# Fuente_Simetrica.net
KiCad netlist of a schematic drawn in Altium Designer
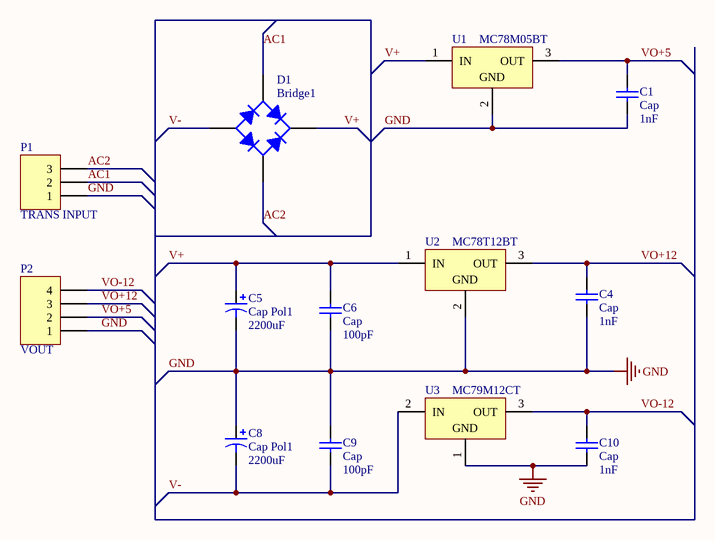
[diagram p0: Fuente Simetrica.SchDoc]

(export (version "E")
  (design (tool "Eeschema 10.0.6"))
  (components
    (comp (ref "C1")
      (value "Cap")
      (footprint "RAD-0.2")
      (description "Capacitor")
      (fields (field (name "ALTIUM_VALUE") "1nF") (field (name "PUBLISHER") "Altium Limited"))
      (libsource (lib "Miscellaneous Devices") (part "Cap"))
    )
    (comp (ref "C4")
      (value "Cap")
      (footprint "RAD-0.2")
      (description "Capacitor")
      (fields (field (name "ALTIUM_VALUE") "1nF") (field (name "PUBLISHER") "Altium Limited"))
      (libsource (lib "Miscellaneous Devices") (part "Cap"))
    )
    (comp (ref "C5")
      (value "Cap Pol1")
      (footprint "RB5-10.5")
      (description "Polarized Capacitor (Radial)")
      (fields (field (name "ALTIUM_VALUE") "2200uF") (field (name "PUBLISHER") "Altium Limited"))
      (libsource (lib "Miscellaneous Devices") (part "Cap Pol1"))
    )
    (comp (ref "C6")
      (value "Cap")
      (footprint "RAD-0.2")
      (description "Capacitor")
      (fields (field (name "ALTIUM_VALUE") "100pF") (field (name "PUBLISHER") "Altium Limited"))
      (libsource (lib "Miscellaneous Devices") (part "Cap"))
    )
    (comp (ref "C8")
      (value "Cap Pol1")
      (footprint "RB5-10.5")
      (description "Polarized Capacitor (Radial)")
      (fields (field (name "ALTIUM_VALUE") "2200uF") (field (name "PUBLISHER") "Altium Limited"))
      (libsource (lib "Miscellaneous Devices") (part "Cap Pol1"))
    )
    (comp (ref "C9")
      (value "Cap")
      (footprint "RAD-0.2")
      (description "Capacitor")
      (fields (field (name "ALTIUM_VALUE") "100pF") (field (name "PUBLISHER") "Altium Limited"))
      (libsource (lib "Miscellaneous Devices") (part "Cap"))
    )
    (comp (ref "C10")
      (value "Cap")
      (footprint "RAD-0.2")
      (description "Capacitor")
      (fields (field (name "ALTIUM_VALUE") "1nF") (field (name "PUBLISHER") "Altium Limited"))
      (libsource (lib "Miscellaneous Devices") (part "Cap"))
    )
    (comp (ref "D1")
      (value "Bridge1")
      (footprint "PUENTE1A")
      (description "Full Wave Diode Bridge")
      (fields (field (name "PUBLISHER") "Altium Limited"))
      (libsource (lib "Miscellaneous Devices") (part "Bridge1"))
    )
    (comp (ref "P1")
      (value "TRANS INPUT")
      (footprint "AZUL5-3")
      (description "Header, 3-Pin")
      (fields (field (name "PUBLISHER") "Altium Limited"))
      (libsource (lib "Miscellaneous Connectors") (part "Header 3"))
    )
    (comp (ref "P2")
      (value "VOUT")
      (footprint "AZUL5-4")
      (description "Header, 4-Pin")
      (fields (field (name "PUBLISHER") "Altium Limited"))
      (libsource (lib "Miscellaneous Connectors") (part "Header 4"))
    )
    (comp (ref "U1")
      (value "MC78M05BT")
      (footprint "221A-04")
      (description "3-Terminal Medium-Current Positive Fixed Voltage Regulator")
      (fields (field (name "PUBLISHER") "Altium Limited"))
      (libsource (lib "Motorola Power Mgt Voltage Regulator") (part "MC78M05BT"))
    )
    (comp (ref "U2")
      (value "MC78T12BT")
      (footprint "221A-04")
      (description "Three-Ampere Positive Fixed Voltage Regulator")
      (fields (field (name "PUBLISHER") "Altium Limited"))
      (libsource (lib "Motorola Power Mgt Voltage Regulator") (part "MC78T12BT"))
    )
    (comp (ref "U3")
      (value "MC79M12CT")
      (footprint "221A-04")
      (description "Three-Terminal Negative Fixed Voltage Regulator")
      (fields (field (name "PUBLISHER") "Altium Limited"))
      (libsource (lib "Motorola Power Mgt Voltage Regulator") (part "MC79M12CT"))
    )
  )
  (nets
    (net (code "1") (name "/AC1") (class "Default")
      (node (ref "D1") (pin "4") (pinfunction "C_4") (pintype "passive"))
      (node (ref "P1") (pin "2") (pinfunction "2_2") (pintype "passive"))
    )
    (net (code "2") (name "/AC2") (class "Default")
      (node (ref "D1") (pin "2") (pinfunction "C_2") (pintype "passive"))
      (node (ref "P1") (pin "3") (pinfunction "3_3") (pintype "passive"))
    )
    (net (code "3") (name "/V+") (class "Default")
      (node (ref "C5") (pin "1") (pinfunction "1_1") (pintype "passive"))
      (node (ref "C6") (pin "2") (pinfunction "2_2") (pintype "passive"))
      (node (ref "D1") (pin "1") (pinfunction "K_1") (pintype "passive"))
      (node (ref "U1") (pin "1") (pinfunction "IN_1") (pintype "power_in"))
      (node (ref "U2") (pin "1") (pinfunction "IN_1") (pintype "power_in"))
    )
    (net (code "4") (name "/V-") (class "Default")
      (node (ref "C8") (pin "2") (pinfunction "2_2") (pintype "passive"))
      (node (ref "C9") (pin "1") (pinfunction "1_1") (pintype "passive"))
      (node (ref "D1") (pin "3") (pinfunction "A_3") (pintype "passive"))
      (node (ref "U3") (pin "2") (pinfunction "IN_2") (pintype "power_in"))
    )
    (net (code "5") (name "/VO+5") (class "Default")
      (node (ref "C1") (pin "2") (pinfunction "2_2") (pintype "passive"))
      (node (ref "P2") (pin "2") (pinfunction "2_2") (pintype "passive"))
      (node (ref "U1") (pin "3") (pinfunction "OUT_3") (pintype "power_in"))
    )
    (net (code "6") (name "/VO+12") (class "Default")
      (node (ref "C4") (pin "2") (pinfunction "2_2") (pintype "passive"))
      (node (ref "P2") (pin "3") (pinfunction "3_3") (pintype "passive"))
      (node (ref "U2") (pin "3") (pinfunction "OUT_3") (pintype "power_in"))
    )
    (net (code "7") (name "/VO-12") (class "Default")
      (node (ref "C10") (pin "2") (pinfunction "2_2") (pintype "passive"))
      (node (ref "P2") (pin "4") (pinfunction "4_4") (pintype "passive"))
      (node (ref "U3") (pin "3") (pinfunction "OUT_3") (pintype "power_in"))
    )
    (net (code "8") (name "GND") (class "Default")
      (node (ref "C1") (pin "1") (pinfunction "1_1") (pintype "passive"))
      (node (ref "C10") (pin "1") (pinfunction "1_1") (pintype "passive"))
      (node (ref "C4") (pin "1") (pinfunction "1_1") (pintype "passive"))
      (node (ref "C5") (pin "2") (pinfunction "2_2") (pintype "passive"))
      (node (ref "C6") (pin "1") (pinfunction "1_1") (pintype "passive"))
      (node (ref "C8") (pin "1") (pinfunction "1_1") (pintype "passive"))
      (node (ref "C9") (pin "2") (pinfunction "2_2") (pintype "passive"))
      (node (ref "P1") (pin "1") (pinfunction "1_1") (pintype "passive"))
      (node (ref "P2") (pin "1") (pinfunction "1_1") (pintype "passive"))
      (node (ref "U1") (pin "2") (pinfunction "GND_2") (pintype "power_in"))
      (node (ref "U2") (pin "2") (pinfunction "GND_2") (pintype "power_in"))
      (node (ref "U3") (pin "1") (pinfunction "GND_1") (pintype "power_in"))
    )
  )
)
